# Servo_Schematic.net
KiCad netlist of a schematic drawn in EAGLE
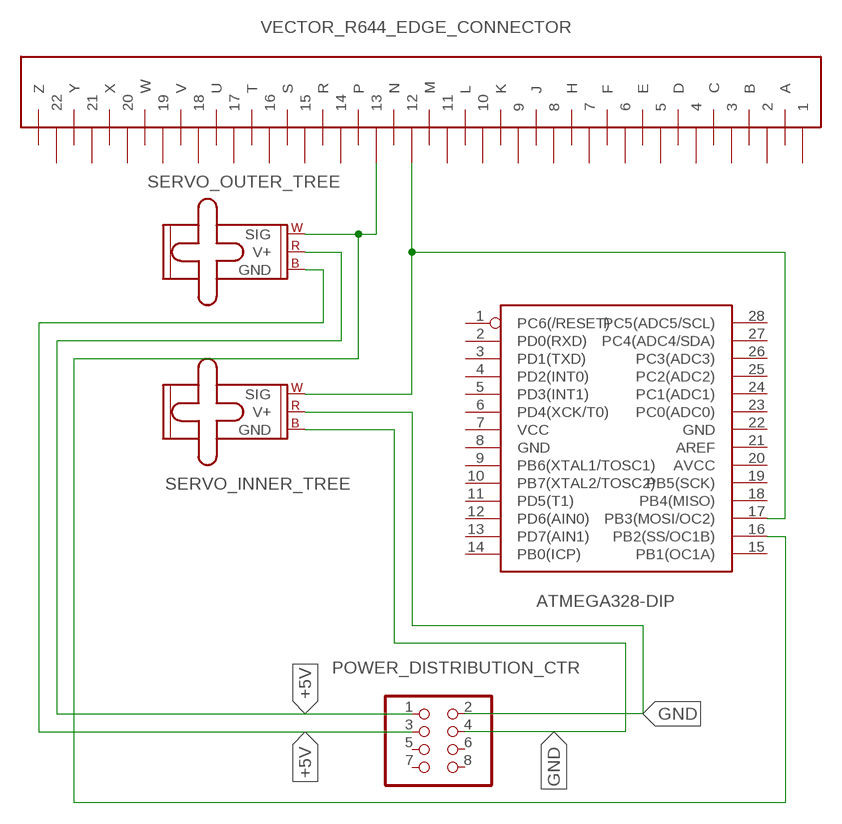
[diagram p0: schematic, sheet 1]

(export (version "E")
  (design (tool "Eeschema 10.0.6"))
  (components
    (comp (ref "POWER_DISTRIBUTION_CTR")
      (value "PINHD-2X4")
      (footprint "eagle-import:2X04")
      (libsource (lib "eagle-import") (part "PINHD-2X4"))
    )
    (comp (ref "SERVO_INNER_TREE")
      (value "SERVO")
      (footprint "eagle-import:1X03")
      (libsource (lib "eagle-import") (part "SERVO"))
    )
    (comp (ref "SERVO_OUTER_TREE")
      (value "SERVO")
      (footprint "eagle-import:1X03")
      (libsource (lib "eagle-import") (part "SERVO"))
    )
    (comp (ref "U$7")
      (value "ATMEGA328-DIP")
      (footprint "eagle-import:DIP28")
      (libsource (lib "eagle-import") (part "ATMEGA328-DIP"))
    )
    (comp (ref "U$8")
      (value "VECTOR_R644_EDGE_CONNECTOR")
      (footprint "eagle-import:VECTOR44")
      (libsource (lib "eagle-import") (part "VECTOR_R644_EDGE_CONNECTOR"))
    )
  )
  (nets
    (net (code "1") (name "+5V") (class "Default")
      (node (ref "POWER_DISTRIBUTION_CTR") (pin "1") (pinfunction "1_1") (pintype "passive"))
      (node (ref "POWER_DISTRIBUTION_CTR") (pin "3") (pinfunction "3_3") (pintype "passive"))
      (node (ref "SERVO_OUTER_TREE") (pin "2") (pinfunction "V+_2") (pintype "bidirectional"))
      (node (ref "SERVO_OUTER_TREE") (pin "3") (pinfunction "GND_3") (pintype "bidirectional"))
    )
    (net (code "2") (name "GND") (class "Default")
      (node (ref "POWER_DISTRIBUTION_CTR") (pin "2") (pinfunction "2_2") (pintype "passive"))
      (node (ref "POWER_DISTRIBUTION_CTR") (pin "4") (pinfunction "4_4") (pintype "passive"))
      (node (ref "SERVO_INNER_TREE") (pin "2") (pinfunction "V+_2") (pintype "bidirectional"))
      (node (ref "SERVO_INNER_TREE") (pin "3") (pinfunction "GND_3") (pintype "bidirectional"))
    )
    (net (code "3") (name "Net-(SERVO_INNER_TREE-SIG)") (class "Default")
      (node (ref "SERVO_INNER_TREE") (pin "1") (pinfunction "SIG_1") (pintype "bidirectional"))
      (node (ref "U$7") (pin "17") (pinfunction "PB3(MOSI/OC2)_17") (pintype "bidirectional"))
      (node (ref "U$8") (pin "P$12") (pinfunction "12_P$12") (pintype "bidirectional"))
    )
    (net (code "4") (name "Net-(SERVO_OUTER_TREE-SIG)") (class "Default")
      (node (ref "SERVO_OUTER_TREE") (pin "1") (pinfunction "SIG_1") (pintype "bidirectional"))
      (node (ref "U$7") (pin "16") (pinfunction "PB2(SS/OC1B)_16") (pintype "bidirectional"))
      (node (ref "U$8") (pin "P$13") (pinfunction "13_P$13") (pintype "bidirectional"))
    )
    (net (code "5") (name "unconnected-(POWER_DISTRIBUTION_CTR-Pad5)") (class "Default")
      (node (ref "POWER_DISTRIBUTION_CTR") (pin "5") (pinfunction "5_5") (pintype "passive"))
    )
    (net (code "6") (name "unconnected-(POWER_DISTRIBUTION_CTR-Pad6)") (class "Default")
      (node (ref "POWER_DISTRIBUTION_CTR") (pin "6") (pinfunction "6_6") (pintype "passive"))
    )
    (net (code "7") (name "unconnected-(POWER_DISTRIBUTION_CTR-Pad7)") (class "Default")
      (node (ref "POWER_DISTRIBUTION_CTR") (pin "7") (pinfunction "7_7") (pintype "passive"))
    )
    (net (code "8") (name "unconnected-(POWER_DISTRIBUTION_CTR-Pad8)") (class "Default")
      (node (ref "POWER_DISTRIBUTION_CTR") (pin "8") (pinfunction "8_8") (pintype "passive"))
    )
    (net (code "9") (name "unconnected-(U$7-AREF-Pad21)") (class "Default")
      (node (ref "U$7") (pin "21") (pinfunction "AREF_21") (pintype "bidirectional"))
    )
    (net (code "10") (name "unconnected-(U$7-AVCC-Pad20)") (class "Default")
      (node (ref "U$7") (pin "20") (pinfunction "AVCC_20") (pintype "bidirectional"))
    )
    (net (code "11") (name "unconnected-(U$7-GND-Pad8)") (class "Default")
      (node (ref "U$7") (pin "8") (pinfunction "GND_8") (pintype "bidirectional"))
    )
    (net (code "12") (name "unconnected-(U$7-GND-Pad22)") (class "Default")
      (node (ref "U$7") (pin "22") (pinfunction "GND_22") (pintype "bidirectional"))
    )
    (net (code "13") (name "unconnected-(U$7-PB0(ICP)-Pad14)") (class "Default")
      (node (ref "U$7") (pin "14") (pinfunction "PB0(ICP)_14") (pintype "bidirectional"))
    )
    (net (code "14") (name "unconnected-(U$7-PB1(OC1A)-Pad15)") (class "Default")
      (node (ref "U$7") (pin "15") (pinfunction "PB1(OC1A)_15") (pintype "bidirectional"))
    )
    (net (code "15") (name "unconnected-(U$7-PB4(MISO)-Pad18)") (class "Default")
      (node (ref "U$7") (pin "18") (pinfunction "PB4(MISO)_18") (pintype "bidirectional"))
    )
    (net (code "16") (name "unconnected-(U$7-PB5(SCK)-Pad19)") (class "Default")
      (node (ref "U$7") (pin "19") (pinfunction "PB5(SCK)_19") (pintype "bidirectional"))
    )
    (net (code "17") (name "unconnected-(U$7-PB6(XTAL1{slash}TOSC1)-Pad9)") (class "Default")
      (node (ref "U$7") (pin "9") (pinfunction "PB6(XTAL1/TOSC1)_9") (pintype "bidirectional"))
    )
    (net (code "18") (name "unconnected-(U$7-PB7(XTAL2{slash}TOSC2)-Pad10)") (class "Default")
      (node (ref "U$7") (pin "10") (pinfunction "PB7(XTAL2/TOSC2)_10") (pintype "bidirectional"))
    )
    (net (code "19") (name "unconnected-(U$7-PC0(ADC0)-Pad23)") (class "Default")
      (node (ref "U$7") (pin "23") (pinfunction "PC0(ADC0)_23") (pintype "bidirectional"))
    )
    (net (code "20") (name "unconnected-(U$7-PC1(ADC1)-Pad24)") (class "Default")
      (node (ref "U$7") (pin "24") (pinfunction "PC1(ADC1)_24") (pintype "bidirectional"))
    )
    (net (code "21") (name "unconnected-(U$7-PC2(ADC2)-Pad25)") (class "Default")
      (node (ref "U$7") (pin "25") (pinfunction "PC2(ADC2)_25") (pintype "bidirectional"))
    )
    (net (code "22") (name "unconnected-(U$7-PC3(ADC3)-Pad26)") (class "Default")
      (node (ref "U$7") (pin "26") (pinfunction "PC3(ADC3)_26") (pintype "bidirectional"))
    )
    (net (code "23") (name "unconnected-(U$7-PC4(ADC4{slash}SDA)-Pad27)") (class "Default")
      (node (ref "U$7") (pin "27") (pinfunction "PC4(ADC4/SDA)_27") (pintype "bidirectional"))
    )
    (net (code "24") (name "unconnected-(U$7-PC5(ADC5{slash}SCL)-Pad28)") (class "Default")
      (node (ref "U$7") (pin "28") (pinfunction "PC5(ADC5/SCL)_28") (pintype "bidirectional"))
    )
    (net (code "25") (name "unconnected-(U$7-PC6({slash}RESET)-Pad1)") (class "Default")
      (node (ref "U$7") (pin "1") (pinfunction "PC6(/RESET)_1") (pintype "bidirectional"))
    )
    (net (code "26") (name "unconnected-(U$7-PD0(RXD)-Pad2)") (class "Default")
      (node (ref "U$7") (pin "2") (pinfunction "PD0(RXD)_2") (pintype "bidirectional"))
    )
    (net (code "27") (name "unconnected-(U$7-PD1(TXD)-Pad3)") (class "Default")
      (node (ref "U$7") (pin "3") (pinfunction "PD1(TXD)_3") (pintype "bidirectional"))
    )
    (net (code "28") (name "unconnected-(U$7-PD2(INT0)-Pad4)") (class "Default")
      (node (ref "U$7") (pin "4") (pinfunction "PD2(INT0)_4") (pintype "bidirectional"))
    )
    (net (code "29") (name "unconnected-(U$7-PD3(INT1)-Pad5)") (class "Default")
      (node (ref "U$7") (pin "5") (pinfunction "PD3(INT1)_5") (pintype "bidirectional"))
    )
    (net (code "30") (name "unconnected-(U$7-PD4(XCK{slash}T0)-Pad6)") (class "Default")
      (node (ref "U$7") (pin "6") (pinfunction "PD4(XCK/T0)_6") (pintype "bidirectional"))
    )
    (net (code "31") (name "unconnected-(U$7-PD5(T1)-Pad11)") (class "Default")
      (node (ref "U$7") (pin "11") (pinfunction "PD5(T1)_11") (pintype "bidirectional"))
    )
    (net (code "32") (name "unconnected-(U$7-PD6(AIN0)-Pad12)") (class "Default")
      (node (ref "U$7") (pin "12") (pinfunction "PD6(AIN0)_12") (pintype "bidirectional"))
    )
    (net (code "33") (name "unconnected-(U$7-PD7(AIN1)-Pad13)") (class "Default")
      (node (ref "U$7") (pin "13") (pinfunction "PD7(AIN1)_13") (pintype "bidirectional"))
    )
    (net (code "34") (name "unconnected-(U$7-VCC-Pad7)") (class "Default")
      (node (ref "U$7") (pin "7") (pinfunction "VCC_7") (pintype "bidirectional"))
    )
    (net (code "35") (name "unconnected-(U$8-1-PadP$1)") (class "Default")
      (node (ref "U$8") (pin "P$1") (pinfunction "1_P$1") (pintype "bidirectional"))
    )
    (net (code "36") (name "unconnected-(U$8-2-PadP$2)") (class "Default")
      (node (ref "U$8") (pin "P$2") (pinfunction "2_P$2") (pintype "bidirectional"))
    )
    (net (code "37") (name "unconnected-(U$8-3-PadP$3)") (class "Default")
      (node (ref "U$8") (pin "P$3") (pinfunction "3_P$3") (pintype "bidirectional"))
    )
    (net (code "38") (name "unconnected-(U$8-4-PadP$4)") (class "Default")
      (node (ref "U$8") (pin "P$4") (pinfunction "4_P$4") (pintype "bidirectional"))
    )
    (net (code "39") (name "unconnected-(U$8-5-PadP$5)") (class "Default")
      (node (ref "U$8") (pin "P$5") (pinfunction "5_P$5") (pintype "bidirectional"))
    )
    (net (code "40") (name "unconnected-(U$8-6-PadP$6)") (class "Default")
      (node (ref "U$8") (pin "P$6") (pinfunction "6_P$6") (pintype "bidirectional"))
    )
    (net (code "41") (name "unconnected-(U$8-7-PadP$7)") (class "Default")
      (node (ref "U$8") (pin "P$7") (pinfunction "7_P$7") (pintype "bidirectional"))
    )
    (net (code "42") (name "unconnected-(U$8-8-PadP$8)") (class "Default")
      (node (ref "U$8") (pin "P$8") (pinfunction "8_P$8") (pintype "bidirectional"))
    )
    (net (code "43") (name "unconnected-(U$8-9-PadP$9)") (class "Default")
      (node (ref "U$8") (pin "P$9") (pinfunction "9_P$9") (pintype "bidirectional"))
    )
    (net (code "44") (name "unconnected-(U$8-10-PadP$10)") (class "Default")
      (node (ref "U$8") (pin "P$10") (pinfunction "10_P$10") (pintype "bidirectional"))
    )
    (net (code "45") (name "unconnected-(U$8-11-PadP$11)") (class "Default")
      (node (ref "U$8") (pin "P$11") (pinfunction "11_P$11") (pintype "bidirectional"))
    )
    (net (code "46") (name "unconnected-(U$8-14-PadP$14)") (class "Default")
      (node (ref "U$8") (pin "P$14") (pinfunction "14_P$14") (pintype "bidirectional"))
    )
    (net (code "47") (name "unconnected-(U$8-15-PadP$15)") (class "Default")
      (node (ref "U$8") (pin "P$15") (pinfunction "15_P$15") (pintype "bidirectional"))
    )
    (net (code "48") (name "unconnected-(U$8-16-PadP$16)") (class "Default")
      (node (ref "U$8") (pin "P$16") (pinfunction "16_P$16") (pintype "bidirectional"))
    )
    (net (code "49") (name "unconnected-(U$8-17-PadP$17)") (class "Default")
      (node (ref "U$8") (pin "P$17") (pinfunction "17_P$17") (pintype "bidirectional"))
    )
    (net (code "50") (name "unconnected-(U$8-18-PadP$18)") (class "Default")
      (node (ref "U$8") (pin "P$18") (pinfunction "18_P$18") (pintype "bidirectional"))
    )
    (net (code "51") (name "unconnected-(U$8-19-PadP$19)") (class "Default")
      (node (ref "U$8") (pin "P$19") (pinfunction "19_P$19") (pintype "bidirectional"))
    )
    (net (code "52") (name "unconnected-(U$8-20-PadP$20)") (class "Default")
      (node (ref "U$8") (pin "P$20") (pinfunction "20_P$20") (pintype "bidirectional"))
    )
    (net (code "53") (name "unconnected-(U$8-21-PadP$21)") (class "Default")
      (node (ref "U$8") (pin "P$21") (pinfunction "21_P$21") (pintype "bidirectional"))
    )
    (net (code "54") (name "unconnected-(U$8-22-PadP$22)") (class "Default")
      (node (ref "U$8") (pin "P$22") (pinfunction "22_P$22") (pintype "bidirectional"))
    )
    (net (code "55") (name "unconnected-(U$8-A-PadP$A)") (class "Default")
      (node (ref "U$8") (pin "P$A") (pinfunction "A_P$A") (pintype "bidirectional"))
    )
    (net (code "56") (name "unconnected-(U$8-B-PadP$B)") (class "Default")
      (node (ref "U$8") (pin "P$B") (pinfunction "B_P$B") (pintype "bidirectional"))
    )
    (net (code "57") (name "unconnected-(U$8-C-PadP$C)") (class "Default")
      (node (ref "U$8") (pin "P$C") (pinfunction "C_P$C") (pintype "bidirectional"))
    )
    (net (code "58") (name "unconnected-(U$8-D-PadP$D)") (class "Default")
      (node (ref "U$8") (pin "P$D") (pinfunction "D_P$D") (pintype "bidirectional"))
    )
    (net (code "59") (name "unconnected-(U$8-E-PadP$E)") (class "Default")
      (node (ref "U$8") (pin "P$E") (pinfunction "E_P$E") (pintype "bidirectional"))
    )
    (net (code "60") (name "unconnected-(U$8-F-PadP$F)") (class "Default")
      (node (ref "U$8") (pin "P$F") (pinfunction "F_P$F") (pintype "bidirectional"))
    )
    (net (code "61") (name "unconnected-(U$8-H-PadP$H)") (class "Default")
      (node (ref "U$8") (pin "P$H") (pinfunction "H_P$H") (pintype "bidirectional"))
    )
    (net (code "62") (name "unconnected-(U$8-J-PadP$J)") (class "Default")
      (node (ref "U$8") (pin "P$J") (pinfunction "J_P$J") (pintype "bidirectional"))
    )
    (net (code "63") (name "unconnected-(U$8-K-PadP$K)") (class "Default")
      (node (ref "U$8") (pin "P$K") (pinfunction "K_P$K") (pintype "bidirectional"))
    )
    (net (code "64") (name "unconnected-(U$8-L-PadP$L)") (class "Default")
      (node (ref "U$8") (pin "P$L") (pinfunction "L_P$L") (pintype "bidirectional"))
    )
    (net (code "65") (name "unconnected-(U$8-M-PadP$M)") (class "Default")
      (node (ref "U$8") (pin "P$M") (pinfunction "M_P$M") (pintype "bidirectional"))
    )
    (net (code "66") (name "unconnected-(U$8-N-PadP$N)") (class "Default")
      (node (ref "U$8") (pin "P$N") (pinfunction "N_P$N") (pintype "bidirectional"))
    )
    (net (code "67") (name "unconnected-(U$8-P-PadP$P)") (class "Default")
      (node (ref "U$8") (pin "P$P") (pinfunction "P_P$P") (pintype "bidirectional"))
    )
    (net (code "68") (name "unconnected-(U$8-R-PadP$R)") (class "Default")
      (node (ref "U$8") (pin "P$R") (pinfunction "R_P$R") (pintype "bidirectional"))
    )
    (net (code "69") (name "unconnected-(U$8-S-PadP$S)") (class "Default")
      (node (ref "U$8") (pin "P$S") (pinfunction "S_P$S") (pintype "bidirectional"))
    )
    (net (code "70") (name "unconnected-(U$8-T-PadP$T)") (class "Default")
      (node (ref "U$8") (pin "P$T") (pinfunction "T_P$T") (pintype "bidirectional"))
    )
    (net (code "71") (name "unconnected-(U$8-U-PadP$U)") (class "Default")
      (node (ref "U$8") (pin "P$U") (pinfunction "U_P$U") (pintype "bidirectional"))
    )
    (net (code "72") (name "unconnected-(U$8-V-PadP$V)") (class "Default")
      (node (ref "U$8") (pin "P$V") (pinfunction "V_P$V") (pintype "bidirectional"))
    )
    (net (code "73") (name "unconnected-(U$8-W-PadP$W)") (class "Default")
      (node (ref "U$8") (pin "P$W") (pinfunction "W_P$W") (pintype "bidirectional"))
    )
    (net (code "74") (name "unconnected-(U$8-X-PadP$X)") (class "Default")
      (node (ref "U$8") (pin "P$X") (pinfunction "X_P$X") (pintype "bidirectional"))
    )
    (net (code "75") (name "unconnected-(U$8-Y-PadP$Y)") (class "Default")
      (node (ref "U$8") (pin "P$Y") (pinfunction "Y_P$Y") (pintype "bidirectional"))
    )
    (net (code "76") (name "unconnected-(U$8-Z-PadP$Z)") (class "Default")
      (node (ref "U$8") (pin "P$Z") (pinfunction "Z_P$Z") (pintype "bidirectional"))
    )
  )
)
